# FanBot.net
KiCad netlist of a schematic drawn in Altium Designer
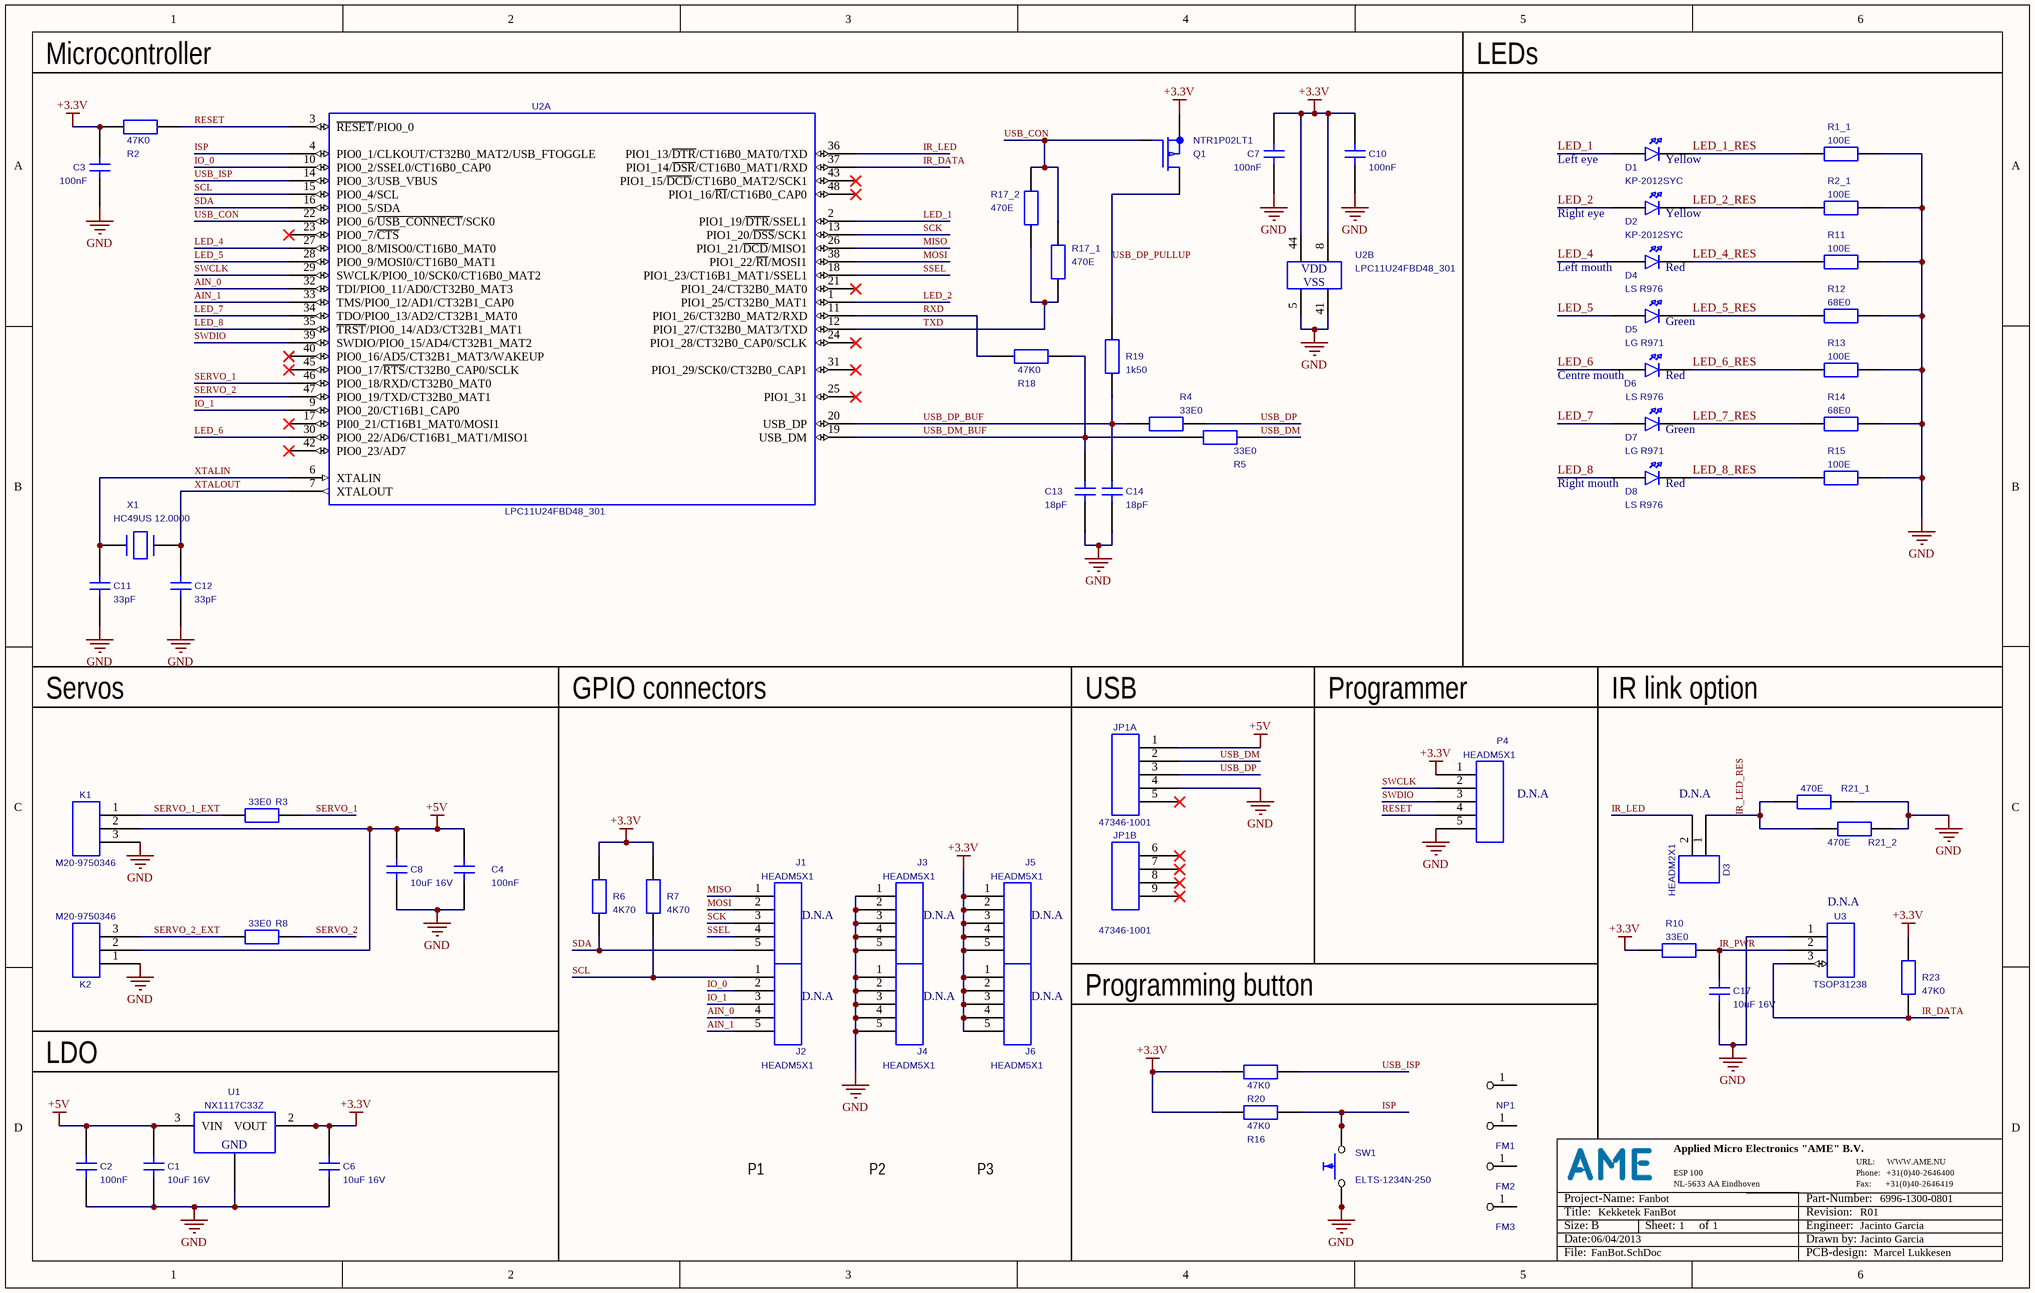
[diagram p0: FanBot.SchDoc]

(export (version "E")
  (design (tool "Eeschema 10.0.6"))
  (components
    (comp (ref "C1")
      (value "10U 0805 X5R16V")
      (footprint "C0805")
      (fields
        (field (name "PART NUMBER") "120400051105")
        (field (name "MANUFACTURER") "AVX")
        (field (name "PVALUE") "10uF 16V")
      )
      (libsource (lib "CC0805") (part "10U 0805 X5R16V"))
    )
    (comp (ref "C2")
      (value "100N 0805 X7R50V")
      (footprint "C0805")
      (fields
        (field (name "PVALUE") "100nF")
        (field (name "PART NUMBER") "120400011003")
        (field (name "MANUFACTURER") "Kemet")
      )
      (libsource (lib "CC0805") (part "100N 0805 X7R50V"))
    )
    (comp (ref "C3")
      (value "100N 0805 X7R50V")
      (footprint "C0805")
      (fields
        (field (name "PVALUE") "100nF")
        (field (name "PART NUMBER") "120400011003")
        (field (name "MANUFACTURER") "Kemet")
      )
      (libsource (lib "CC0805") (part "100N 0805 X7R50V"))
    )
    (comp (ref "C4")
      (value "100N 0805 X7R50V")
      (footprint "C0805")
      (fields
        (field (name "PVALUE") "100nF")
        (field (name "PART NUMBER") "120400011003")
        (field (name "MANUFACTURER") "Kemet")
      )
      (libsource (lib "CC0805") (part "100N 0805 X7R50V"))
    )
    (comp (ref "C6")
      (value "10U 0805 X5R16V")
      (footprint "C0805")
      (fields
        (field (name "PART NUMBER") "120400051105")
        (field (name "MANUFACTURER") "AVX")
        (field (name "PVALUE") "10uF 16V")
      )
      (libsource (lib "CC0805") (part "10U 0805 X5R16V"))
    )
    (comp (ref "C7")
      (value "100N 0805 X7R50V")
      (footprint "C0805")
      (fields
        (field (name "PVALUE") "100nF")
        (field (name "PART NUMBER") "120400011003")
        (field (name "MANUFACTURER") "Kemet")
      )
      (libsource (lib "CC0805") (part "100N 0805 X7R50V"))
    )
    (comp (ref "C8")
      (value "10U 0805 X5R16V")
      (footprint "C0805")
      (fields
        (field (name "PART NUMBER") "120400051105")
        (field (name "MANUFACTURER") "AVX")
        (field (name "PVALUE") "10uF 16V")
      )
      (libsource (lib "CC0805") (part "10U 0805 X5R16V"))
    )
    (comp (ref "C10")
      (value "100N 0805 X7R50V")
      (footprint "C0805")
      (fields
        (field (name "PVALUE") "100nF")
        (field (name "PART NUMBER") "120400011003")
        (field (name "MANUFACTURER") "Kemet")
      )
      (libsource (lib "CC0805") (part "100N 0805 X7R50V"))
    )
    (comp (ref "C11")
      (value "33P 0805 X7R50V")
      (footprint "C0805")
      (fields
        (field (name "PVALUE") "33pF")
        (field (name "PART NUMBER") "120400013309")
        (field (name "MANUFACTURER") "Kemet")
      )
      (libsource (lib "CC0805") (part "33P 0805 X7R50V"))
    )
    (comp (ref "C12")
      (value "33P 0805 X7R50V")
      (footprint "C0805")
      (fields
        (field (name "PVALUE") "33pF")
        (field (name "PART NUMBER") "120400013309")
        (field (name "MANUFACTURER") "Kemet")
      )
      (libsource (lib "CC0805") (part "33P 0805 X7R50V"))
    )
    (comp (ref "C13")
      (value "18P 0805 X7R50V")
      (footprint "C0805")
      (fields
        (field (name "PVALUE") "18pF")
        (field (name "PART NUMBER") "120400011809")
        (field (name "MANUFACTURER") "Kemet")
      )
      (libsource (lib "CC0805") (part "18P 0805 X7R50V"))
    )
    (comp (ref "C14")
      (value "18P 0805 X7R50V")
      (footprint "C0805")
      (fields
        (field (name "PVALUE") "18pF")
        (field (name "PART NUMBER") "120400011809")
        (field (name "MANUFACTURER") "Kemet")
      )
      (libsource (lib "CC0805") (part "18P 0805 X7R50V"))
    )
    (comp (ref "C17")
      (value "10U 0805 X5R16V")
      (footprint "C0805")
      (fields
        (field (name "PART NUMBER") "120400051105")
        (field (name "MANUFACTURER") "AVX")
        (field (name "PVALUE") "10uF 16V")
      )
      (libsource (lib "CC0805") (part "10U 0805 X5R16V"))
    )
    (comp (ref "D1")
      (value "KP-2012SYC")
      (footprint "0805 LED")
      (fields (field (name "PART NUMBER") "206000010035") (field (name "MANUFACTURER") "Kingbright"))
      (libsource (lib "DIS_AM") (part "KP-2012SYC"))
    )
    (comp (ref "D2")
      (value "KP-2012SYC")
      (footprint "0805 LED")
      (fields (field (name "PART NUMBER") "206000010035") (field (name "MANUFACTURER") "Kingbright"))
      (libsource (lib "DIS_AM") (part "KP-2012SYC"))
    )
    (comp (ref "D3")
      (value "HEADM2X1")
      (footprint "HEADM2X1")
      (fields (field (name "PART NUMBER") "505000030003") (field (name "MANUFACTURER") "Harwin"))
      (libsource (lib "CONN_AM") (part "HEADM2X1"))
    )
    (comp (ref "D4")
      (value "LS R976")
      (footprint "0805 LED OSR")
      (fields (field (name "PART NUMBER") "206000010024") (field (name "MANUFACTURER") "Osram"))
      (libsource (lib "DIS_AM") (part "LS R976"))
    )
    (comp (ref "D5")
      (value "LG R971")
      (footprint "0805 LED OSR")
      (fields (field (name "PART NUMBER") "206000010001") (field (name "MANUFACTURER") "Osram"))
      (libsource (lib "DIS_AM") (part "LG R971"))
    )
    (comp (ref "D6")
      (value "LS R976")
      (footprint "0805 LED OSR")
      (fields (field (name "PART NUMBER") "206000010024") (field (name "MANUFACTURER") "Osram"))
      (libsource (lib "DIS_AM") (part "LS R976"))
    )
    (comp (ref "D7")
      (value "LG R971")
      (footprint "0805 LED OSR")
      (fields (field (name "PART NUMBER") "206000010001") (field (name "MANUFACTURER") "Osram"))
      (libsource (lib "DIS_AM") (part "LG R971"))
    )
    (comp (ref "D8")
      (value "LS R976")
      (footprint "0805 LED OSR")
      (fields (field (name "PART NUMBER") "206000010024") (field (name "MANUFACTURER") "Osram"))
      (libsource (lib "DIS_AM") (part "LS R976"))
    )
    (comp (ref "FM1")
      (value "FIDUCIAL MARK 1")
      (footprint "FIDUCIAL MARK 1")
      (libsource (lib "SCH") (part "FIDUCIAL MARK 1"))
    )
    (comp (ref "FM2")
      (value "FIDUCIAL MARK 1")
      (footprint "FIDUCIAL MARK 1")
      (libsource (lib "SCH") (part "FIDUCIAL MARK 1"))
    )
    (comp (ref "FM3")
      (value "FIDUCIAL MARK 1")
      (footprint "FIDUCIAL MARK 1")
      (libsource (lib "SCH") (part "FIDUCIAL MARK 1"))
    )
    (comp (ref "J1")
      (value "HEADM5X1")
      (footprint "M20-9770522")
      (fields (field (name "PART NUMBER") "505000080023") (field (name "MANUFACTURER") "Harwin"))
      (libsource (lib "CONN_AM") (part "HEADM5X1"))
    )
    (comp (ref "J2")
      (value "HEADM5X1")
      (footprint "M20-9770522")
      (fields (field (name "PART NUMBER") "505000080023") (field (name "MANUFACTURER") "Harwin"))
      (libsource (lib "CONN_AM") (part "HEADM5X1"))
    )
    (comp (ref "J3")
      (value "HEADM5X1")
      (footprint "M20-9770522")
      (fields (field (name "PART NUMBER") "505000080023") (field (name "MANUFACTURER") "Harwin"))
      (libsource (lib "CONN_AM") (part "HEADM5X1"))
    )
    (comp (ref "J4")
      (value "HEADM5X1")
      (footprint "M20-9770522")
      (fields (field (name "PART NUMBER") "505000080023") (field (name "MANUFACTURER") "Harwin"))
      (libsource (lib "CONN_AM") (part "HEADM5X1"))
    )
    (comp (ref "J5")
      (value "HEADM5X1")
      (footprint "M20-9770522")
      (fields (field (name "PART NUMBER") "505000080023") (field (name "MANUFACTURER") "Harwin"))
      (libsource (lib "CONN_AM") (part "HEADM5X1"))
    )
    (comp (ref "J6")
      (value "HEADM5X1")
      (footprint "M20-9770522")
      (fields (field (name "PART NUMBER") "505000080023") (field (name "MANUFACTURER") "Harwin"))
      (libsource (lib "CONN_AM") (part "HEADM5X1"))
    )
    (comp (ref "JP1")
      (value "47346-1001")
      (footprint "47346-0001")
      (fields (field (name "PART NUMBER") "509000220067") (field (name "MANUFACTURER") "Molex"))
      (libsource (lib "CONN_AM") (part "47346-1001"))
    )
    (comp (ref "K1")
      (value "M20-9750346")
      (footprint "M20-9750346")
      (fields (field (name "PART NUMBER") "505000080120") (field (name "MANUFACTURER") "Harwin"))
      (libsource (lib "CONN_AM") (part "M20-9750346"))
    )
    (comp (ref "K2")
      (value "M20-9750346")
      (footprint "M20-9750346")
      (fields (field (name "PART NUMBER") "505000080120") (field (name "MANUFACTURER") "Harwin"))
      (libsource (lib "CONN_AM") (part "M20-9750346"))
    )
    (comp (ref "NP1") (value "NULPUNT") (footprint "NULPUNT") (libsource (lib "SCH") (part "NULPUNT")))
    (comp (ref "P4")
      (value "HEADM5X1")
      (footprint "M20-9770522")
      (fields (field (name "PART NUMBER") "505000080023") (field (name "MANUFACTURER") "Harwin"))
      (libsource (lib "CONN_AM") (part "HEADM5X1"))
    )
    (comp (ref "Q1")
      (value "NTR1P02LT1")
      (footprint "SOT-23")
      (fields (field (name "PART NUMBER") "222000010018") (field (name "MANUFACTURER") "ON Semiconductor"))
      (libsource (lib "DIS_AM") (part "NTR1P02LT1"))
    )
    (comp (ref "R1_1")
      (value "100E 0805 1%")
      (footprint "R0805")
      (fields
        (field (name "PVALUE") "100E")
        (field (name "PART NUMBER") "110200011000")
        (field (name "MANUFACTURER") "ASJ")
      )
      (libsource (lib "RM08051") (part "100E 0805 1%"))
    )
    (comp (ref "R2")
      (value "47K0 0805 1%")
      (footprint "R0805")
      (fields
        (field (name "PVALUE") "47K0")
        (field (name "PART NUMBER") "110200014702")
        (field (name "MANUFACTURER") "ASJ")
      )
      (libsource (lib "RM08051") (part "47K0 0805 1%"))
    )
    (comp (ref "R2_1")
      (value "100E 0805 1%")
      (footprint "R0805")
      (fields
        (field (name "PVALUE") "100E")
        (field (name "PART NUMBER") "110200011000")
        (field (name "MANUFACTURER") "ASJ")
      )
      (libsource (lib "RM08051") (part "100E 0805 1%"))
    )
    (comp (ref "R3")
      (value "33E0 0805 1%")
      (footprint "R0805")
      (fields
        (field (name "PART NUMBER") "110200013309")
        (field (name "MANUFACTURER") "Yageo")
        (field (name "PVALUE") "33E0")
      )
      (libsource (lib "RM08051") (part "33E0 0805 1%"))
    )
    (comp (ref "R4")
      (value "33E0 0805 1%")
      (footprint "R0805")
      (fields
        (field (name "PART NUMBER") "110200013309")
        (field (name "MANUFACTURER") "Yageo")
        (field (name "PVALUE") "33E0")
      )
      (libsource (lib "RM08051") (part "33E0 0805 1%"))
    )
    (comp (ref "R5")
      (value "33E0 0805 1%")
      (footprint "R0805")
      (fields
        (field (name "PART NUMBER") "110200013309")
        (field (name "MANUFACTURER") "Yageo")
        (field (name "PVALUE") "33E0")
      )
      (libsource (lib "RM08051") (part "33E0 0805 1%"))
    )
    (comp (ref "R6")
      (value "4K70 0805 1%")
      (footprint "R0805")
      (fields
        (field (name "PVALUE") "4K70")
        (field (name "PART NUMBER") "110200014701")
        (field (name "MANUFACTURER") "ASJ")
      )
      (libsource (lib "RM08051") (part "4K70 0805 1%"))
    )
    (comp (ref "R7")
      (value "4K70 0805 1%")
      (footprint "R0805")
      (fields
        (field (name "PVALUE") "4K70")
        (field (name "PART NUMBER") "110200014701")
        (field (name "MANUFACTURER") "ASJ")
      )
      (libsource (lib "RM08051") (part "4K70 0805 1%"))
    )
    (comp (ref "R8")
      (value "33E0 0805 1%")
      (footprint "R0805")
      (fields
        (field (name "PART NUMBER") "110200013309")
        (field (name "MANUFACTURER") "Yageo")
        (field (name "PVALUE") "33E0")
      )
      (libsource (lib "RM08051") (part "33E0 0805 1%"))
    )
    (comp (ref "R10")
      (value "33E0 0805 1%")
      (footprint "R0805")
      (fields
        (field (name "PVALUE") "33E0")
        (field (name "PART NUMBER") "110200013309")
        (field (name "MANUFACTURER") "Yageo")
      )
      (libsource (lib "RM08051") (part "33E0 0805 1%"))
    )
    (comp (ref "R11")
      (value "100E 0805 1%")
      (footprint "R0805")
      (fields
        (field (name "PVALUE") "100E")
        (field (name "PART NUMBER") "110200011000")
        (field (name "MANUFACTURER") "ASJ")
      )
      (libsource (lib "RM08051") (part "100E 0805 1%"))
    )
    (comp (ref "R12")
      (value "68E0 0805 1%")
      (footprint "R0805")
      (fields
        (field (name "PVALUE") "68E0")
        (field (name "PART NUMBER") "110200016809")
        (field (name "MANUFACTURER") "ASJ")
      )
      (libsource (lib "RM08051") (part "68E0 0805 1%"))
    )
    (comp (ref "R13")
      (value "100E 0805 1%")
      (footprint "R0805")
      (fields
        (field (name "PVALUE") "100E")
        (field (name "PART NUMBER") "110200011000")
        (field (name "MANUFACTURER") "ASJ")
      )
      (libsource (lib "RM08051") (part "100E 0805 1%"))
    )
    (comp (ref "R14")
      (value "68E0 0805 1%")
      (footprint "R0805")
      (fields
        (field (name "PVALUE") "68E0")
        (field (name "PART NUMBER") "110200016809")
        (field (name "MANUFACTURER") "ASJ")
      )
      (libsource (lib "RM08051") (part "68E0 0805 1%"))
    )
    (comp (ref "R15")
      (value "100E 0805 1%")
      (footprint "R0805")
      (fields
        (field (name "PVALUE") "100E")
        (field (name "PART NUMBER") "110200011000")
        (field (name "MANUFACTURER") "ASJ")
      )
      (libsource (lib "RM08051") (part "100E 0805 1%"))
    )
    (comp (ref "R16")
      (value "47K0 0805 1%")
      (footprint "R0805")
      (fields
        (field (name "PVALUE") "47K0")
        (field (name "PART NUMBER") "110200014702")
        (field (name "MANUFACTURER") "ASJ")
      )
      (libsource (lib "RM08051") (part "47K0 0805 1%"))
    )
    (comp (ref "R17_1")
      (value "470E 0805 1%")
      (footprint "R0805")
      (fields
        (field (name "PVALUE") "470E")
        (field (name "PART NUMBER") "110200014700")
        (field (name "MANUFACTURER") "ASJ")
      )
      (libsource (lib "RM08051") (part "470E 0805 1%"))
    )
    (comp (ref "R17_2")
      (value "470E 0805 1%")
      (footprint "R0805")
      (fields
        (field (name "PVALUE") "470E")
        (field (name "PART NUMBER") "110200014700")
        (field (name "MANUFACTURER") "ASJ")
      )
      (libsource (lib "RM08051") (part "470E 0805 1%"))
    )
    (comp (ref "R18")
      (value "47K0 0805 1%")
      (footprint "R0805")
      (fields
        (field (name "PVALUE") "47K0")
        (field (name "PART NUMBER") "110200014702")
        (field (name "MANUFACTURER") "ASJ")
      )
      (libsource (lib "RM08051") (part "47K0 0805 1%"))
    )
    (comp (ref "R19")
      (value "1K50 0805 1%")
      (footprint "R0805")
      (fields
        (field (name "PVALUE") "1k50")
        (field (name "PART NUMBER") "110200011501")
        (field (name "MANUFACTURER") "ASJ")
      )
      (libsource (lib "RM08051") (part "1K50 0805 1%"))
    )
    (comp (ref "R20")
      (value "47K0 0805 1%")
      (footprint "R0805")
      (fields
        (field (name "PVALUE") "47K0")
        (field (name "PART NUMBER") "110200014702")
        (field (name "MANUFACTURER") "ASJ")
      )
      (libsource (lib "RM08051") (part "47K0 0805 1%"))
    )
    (comp (ref "R21_1")
      (value "470E 0805 1%")
      (footprint "R0805")
      (fields
        (field (name "PVALUE") "470E")
        (field (name "PART NUMBER") "110200014700")
        (field (name "MANUFACTURER") "ASJ")
      )
      (libsource (lib "RM08051") (part "470E 0805 1%"))
    )
    (comp (ref "R21_2")
      (value "470E 0805 1%")
      (footprint "R0805")
      (fields
        (field (name "PVALUE") "470E")
        (field (name "PART NUMBER") "110200014700")
        (field (name "MANUFACTURER") "ASJ")
      )
      (libsource (lib "RM08051") (part "470E 0805 1%"))
    )
    (comp (ref "R23")
      (value "47K0 0805 1%")
      (footprint "R0805")
      (fields
        (field (name "PVALUE") "47K0")
        (field (name "PART NUMBER") "110200014702")
        (field (name "MANUFACTURER") "ASJ")
      )
      (libsource (lib "RM08051") (part "47K0 0805 1%"))
    )
    (comp (ref "SW1")
      (value "ELTS-1234N-250")
      (footprint "ELTS-1234N")
      (fields (field (name "PART NUMBER") "513000010022") (field (name "MANUFACTURER") "Eledis"))
      (libsource (lib "ELEC_AM") (part "ELTS-1234N-250"))
    )
    (comp (ref "U1")
      (value "NX1117C33Z")
      (footprint "SOT-223")
      (fields (field (name "PART NUMBER") "330000010048") (field (name "MANUFACTURER") "NXP Semiconductor"))
      (libsource (lib "REGULATORS") (part "NX1117C33Z"))
    )
    (comp (ref "U2")
      (value "LPC11U24FBD48_301")
      (footprint "LQFP48")
      (fields (field (name "PART NUMBER") "411000010007") (field (name "MANUFACTURER") "NXP Semiconductor"))
      (libsource (lib "MICRO") (part "LPC11U24FBD48_301"))
    )
    (comp (ref "U3")
      (value "TSOP31238")
      (footprint "TSOP312")
      (fields (field (name "PART NUMBER") "324000010007") (field (name "MANUFACTURER") "Vishay"))
      (libsource (lib "DIS_AM") (part "TSOP31238"))
    )
    (comp (ref "X1")
      (value "HC49US 12.0000")
      (footprint "HC49/4HSMX")
      (fields (field (name "PART NUMBER") "140000010015") (field (name "MANUFACTURER") "Hong Kong Crystals"))
      (libsource (lib "XTAL") (part "HC49US 12.0000"))
    )
  )
  (nets
    (net (code "1") (name "+3.3V") (class "Default")
      (node (ref "C10") (pin "1") (pinfunction "1_1") (pintype "passive"))
      (node (ref "C3") (pin "1") (pinfunction "1_1") (pintype "passive"))
      (node (ref "C6") (pin "1") (pinfunction "1_1") (pintype "passive"))
      (node (ref "C7") (pin "1") (pinfunction "1_1") (pintype "passive"))
      (node (ref "J5") (pin "1") (pinfunction "A1_1") (pintype "passive"))
      (node (ref "J5") (pin "2") (pinfunction "A2_2") (pintype "passive"))
      (node (ref "J5") (pin "3") (pinfunction "A3_3") (pintype "passive"))
      (node (ref "J5") (pin "4") (pinfunction "A4_4") (pintype "passive"))
      (node (ref "J5") (pin "5") (pinfunction "A5_5") (pintype "passive"))
      (node (ref "J6") (pin "1") (pinfunction "A1_1") (pintype "passive"))
      (node (ref "J6") (pin "2") (pinfunction "A2_2") (pintype "passive"))
      (node (ref "J6") (pin "3") (pinfunction "A3_3") (pintype "passive"))
      (node (ref "J6") (pin "4") (pinfunction "A4_4") (pintype "passive"))
      (node (ref "J6") (pin "5") (pinfunction "A5_5") (pintype "passive"))
      (node (ref "P4") (pin "1") (pinfunction "A1_1") (pintype "passive"))
      (node (ref "Q1") (pin "2") (pinfunction "S_2") (pintype "passive"))
      (node (ref "R10") (pin "1") (pinfunction "1_1") (pintype "passive"))
      (node (ref "R16") (pin "2") (pinfunction "2_2") (pintype "passive"))
      (node (ref "R2") (pin "2") (pinfunction "2_2") (pintype "passive"))
      (node (ref "R20") (pin "2") (pinfunction "2_2") (pintype "passive"))
      (node (ref "R23") (pin "1") (pinfunction "1_1") (pintype "passive"))
      (node (ref "R6") (pin "1") (pinfunction "1_1") (pintype "passive"))
      (node (ref "R7") (pin "1") (pinfunction "1_1") (pintype "passive"))
      (node (ref "U1") (pin "2") (pinfunction "VOUT_2") (pintype "power_in"))
      (node (ref "U1") (pin "4") (pinfunction "VOUT_4") (pintype "power_in"))
      (node (ref "U2") (pin "44") (pinfunction "VDD_44") (pintype "power_in"))
      (node (ref "U2") (pin "8") (pinfunction "VDD_8") (pintype "power_in"))
    )
    (net (code "2") (name "+5V") (class "Default")
      (node (ref "C1") (pin "1") (pinfunction "1_1") (pintype "passive"))
      (node (ref "C2") (pin "1") (pinfunction "1_1") (pintype "passive"))
      (node (ref "C4") (pin "1") (pinfunction "1_1") (pintype "passive"))
      (node (ref "C8") (pin "1") (pinfunction "1_1") (pintype "passive"))
      (node (ref "JP1") (pin "1") (pinfunction "VBUS_1") (pintype "passive"))
      (node (ref "K1") (pin "2") (pinfunction "2_2") (pintype "passive"))
      (node (ref "K2") (pin "2") (pinfunction "2_2") (pintype "passive"))
      (node (ref "U1") (pin "3") (pinfunction "VIN_3") (pintype "power_in"))
    )
    (net (code "3") (name "/AIN_0") (class "Default")
      (node (ref "J2") (pin "4") (pinfunction "A4_4") (pintype "passive"))
      (node (ref "U2") (pin "32") (pinfunction "TDI/PIO0_11/AD0/CT32B0_MAT3_32") (pintype "bidirectional"))
    )
    (net (code "4") (name "/AIN_1") (class "Default")
      (node (ref "J2") (pin "5") (pinfunction "A5_5") (pintype "passive"))
      (node (ref "U2") (pin "33") (pinfunction "TMS/PIO0_12/AD1/CT32B1_CAP0_33") (pintype "bidirectional"))
    )
    (net (code "5") (name "/IO_0") (class "Default")
      (node (ref "J2") (pin "2") (pinfunction "A2_2") (pintype "passive"))
      (node (ref "U2") (pin "10") (pinfunction "PIO0_2/SSEL0/CT16B0_CAP0_10") (pintype "bidirectional"))
    )
    (net (code "6") (name "/IO_1") (class "Default")
      (node (ref "J2") (pin "3") (pinfunction "A3_3") (pintype "passive"))
      (node (ref "U2") (pin "9") (pinfunction "PIO0_20/CT16B1_CAP0_9") (pintype "bidirectional"))
    )
    (net (code "7") (name "/IR_DATA") (class "Default")
      (node (ref "R23") (pin "2") (pinfunction "2_2") (pintype "passive"))
      (node (ref "U2") (pin "37") (pinfunction "PIO1_14/~{DSR}/CT16B0_MAT1/RXD_37") (pintype "bidirectional"))
      (node (ref "U3") (pin "3") (pinfunction "OUT_3") (pintype "bidirectional"))
    )
    (net (code "8") (name "/IR_LED") (class "Default")
      (node (ref "D3") (pin "2") (pintype "passive"))
      (node (ref "U2") (pin "36") (pinfunction "PIO1_13/~{DTR}/CT16B0_MAT0/TXD_36") (pintype "bidirectional"))
    )
    (net (code "9") (name "/IR_LED_RES") (class "Default")
      (node (ref "D3") (pin "1") (pintype "passive"))
      (node (ref "R21_1") (pin "1") (pinfunction "1_1") (pintype "passive"))
      (node (ref "R21_2") (pin "1") (pinfunction "1_1") (pintype "passive"))
    )
    (net (code "10") (name "/IR_PWR") (class "Default")
      (node (ref "C17") (pin "1") (pinfunction "1_1") (pintype "passive"))
      (node (ref "R10") (pin "2") (pinfunction "2_2") (pintype "passive"))
      (node (ref "U3") (pin "2") (pinfunction "VS_2") (pintype "power_in"))
    )
    (net (code "11") (name "/ISP") (class "Default")
      (node (ref "R16") (pin "1") (pinfunction "1_1") (pintype "passive"))
      (node (ref "SW1") (pin "1") (pintype "passive"))
      (node (ref "SW1") (pin "3") (pintype "passive"))
      (node (ref "U2") (pin "4") (pinfunction "PIO0_1/CLKOUT/CT32B0_MAT2/USB_FTOGGLE_4") (pintype "bidirectional"))
    )
    (net (code "12") (name "/LED_1") (class "Default")
      (node (ref "D1") (pin "2") (pinfunction "A_2") (pintype "passive"))
      (node (ref "U2") (pin "2") (pinfunction "PIO1_19/~{DTR}/SSEL1_2") (pintype "bidirectional"))
    )
    (net (code "13") (name "/LED_1_RES") (class "Default")
      (node (ref "D1") (pin "1") (pinfunction "K_1") (pintype "passive"))
      (node (ref "R1_1") (pin "1") (pinfunction "1_1") (pintype "passive"))
    )
    (net (code "14") (name "/LED_2") (class "Default")
      (node (ref "D2") (pin "2") (pinfunction "A_2") (pintype "passive"))
      (node (ref "U2") (pin "1") (pinfunction "PIO1_25/CT32B0_MAT1_1") (pintype "bidirectional"))
    )
    (net (code "15") (name "/LED_2_RES") (class "Default")
      (node (ref "D2") (pin "1") (pinfunction "K_1") (pintype "passive"))
      (node (ref "R2_1") (pin "1") (pinfunction "1_1") (pintype "passive"))
    )
    (net (code "16") (name "/LED_4") (class "Default")
      (node (ref "D4") (pin "2") (pinfunction "A_2") (pintype "passive"))
      (node (ref "U2") (pin "27") (pinfunction "PIO0_8/MISO0/CT16B0_MAT0_27") (pintype "bidirectional"))
    )
    (net (code "17") (name "/LED_4_RES") (class "Default")
      (node (ref "D4") (pin "1") (pinfunction "K_1") (pintype "passive"))
      (node (ref "R11") (pin "1") (pinfunction "1_1") (pintype "passive"))
    )
    (net (code "18") (name "/LED_5") (class "Default")
      (node (ref "D5") (pin "2") (pinfunction "A_2") (pintype "passive"))
      (node (ref "U2") (pin "28") (pinfunction "PIO0_9/MOSI0/CT16B0_MAT1_28") (pintype "bidirectional"))
    )
    (net (code "19") (name "/LED_5_RES") (class "Default")
      (node (ref "D5") (pin "1") (pinfunction "K_1") (pintype "passive"))
      (node (ref "R12") (pin "1") (pinfunction "1_1") (pintype "passive"))
    )
    (net (code "20") (name "/LED_6") (class "Default")
      (node (ref "D6") (pin "2") (pinfunction "A_2") (pintype "passive"))
      (node (ref "U2") (pin "30") (pinfunction "PIO0_22/AD6/CT16B1_MAT1/MISO1_30") (pintype "bidirectional"))
    )
    (net (code "21") (name "/LED_6_RES") (class "Default")
      (node (ref "D6") (pin "1") (pinfunction "K_1") (pintype "passive"))
      (node (ref "R13") (pin "1") (pinfunction "1_1") (pintype "passive"))
    )
    (net (code "22") (name "/LED_7") (class "Default")
      (node (ref "D7") (pin "2") (pinfunction "A_2") (pintype "passive"))
      (node (ref "U2") (pin "34") (pinfunction "TDO/PIO0_13/AD2/CT32B1_MAT0_34") (pintype "bidirectional"))
    )
    (net (code "23") (name "/LED_7_RES") (class "Default")
      (node (ref "D7") (pin "1") (pinfunction "K_1") (pintype "passive"))
      (node (ref "R14") (pin "1") (pinfunction "1_1") (pintype "passive"))
    )
    (net (code "24") (name "/LED_8") (class "Default")
      (node (ref "D8") (pin "2") (pinfunction "A_2") (pintype "passive"))
      (node (ref "U2") (pin "35") (pinfunction "~{TRST}/PIO0_14/AD3/CT32B1_MAT1_35") (pintype "bidirectional"))
    )
    (net (code "25") (name "/LED_8_RES") (class "Default")
      (node (ref "D8") (pin "1") (pinfunction "K_1") (pintype "passive"))
      (node (ref "R15") (pin "1") (pinfunction "1_1") (pintype "passive"))
    )
    (net (code "26") (name "/MISO") (class "Default")
      (node (ref "J1") (pin "1") (pinfunction "A1_1") (pintype "passive"))
      (node (ref "U2") (pin "26") (pinfunction "PIO1_21/~{DCD}/MISO1_26") (pintype "bidirectional"))
    )
    (net (code "27") (name "/MOSI") (class "Default")
      (node (ref "J1") (pin "2") (pinfunction "A2_2") (pintype "passive"))
      (node (ref "U2") (pin "38") (pinfunction "PIO1_22/~{RI}/MOSI1_38") (pintype "bidirectional"))
    )
    (net (code "28") (name "/RESET") (class "Default")
      (node (ref "P4") (pin "4") (pinfunction "A4_4") (pintype "passive"))
      (node (ref "R2") (pin "1") (pinfunction "1_1") (pintype "passive"))
      (node (ref "U2") (pin "3") (pinfunction "~{RESET}/PIO0_0_3") (pintype "bidirectional"))
    )
    (net (code "29") (name "/RXD") (class "Default")
      (node (ref "R18") (pin "2") (pinfunction "2_2") (pintype "passive"))
      (node (ref "U2") (pin "11") (pinfunction "PIO1_26/CT32B0_MAT2/RXD_11") (pintype "bidirectional"))
    )
    (net (code "30") (name "/SCK") (class "Default")
      (node (ref "J1") (pin "3") (pinfunction "A3_3") (pintype "passive"))
      (node (ref "U2") (pin "13") (pinfunction "PIO1_20/~{DSS}/SCK1_13") (pintype "bidirectional"))
    )
    (net (code "31") (name "/SCL") (class "Default")
      (node (ref "J2") (pin "1") (pinfunction "A1_1") (pintype "passive"))
      (node (ref "R7") (pin "2") (pinfunction "2_2") (pintype "passive"))
      (node (ref "U2") (pin "15") (pinfunction "PIO0_4/SCL_15") (pintype "bidirectional"))
    )
    (net (code "32") (name "/SDA") (class "Default")
      (node (ref "J1") (pin "5") (pinfunction "A5_5") (pintype "passive"))
      (node (ref "R6") (pin "2") (pinfunction "2_2") (pintype "passive"))
      (node (ref "U2") (pin "16") (pinfunction "PIO0_5/SDA_16") (pintype "bidirectional"))
    )
    (net (code "33") (name "/SERVO_1") (class "Default")
      (node (ref "R3") (pin "2") (pinfunction "2_2") (pintype "passive"))
      (node (ref "U2") (pin "46") (pinfunction "PIO0_18/RXD/CT32B0_MAT0_46") (pintype "bidirectional"))
    )
    (net (code "34") (name "/SERVO_1_EXT") (class "Default")
      (node (ref "K1") (pin "1") (pinfunction "1_1") (pintype "passive"))
      (node (ref "R3") (pin "1") (pinfunction "1_1") (pintype "passive"))
    )
    (net (code "35") (name "/SERVO_2") (class "Default")
      (node (ref "R8") (pin "2") (pinfunction "2_2") (pintype "passive"))
      (node (ref "U2") (pin "47") (pinfunction "PIO0_19/TXD/CT32B0_MAT1_47") (pintype "bidirectional"))
    )
    (net (code "36") (name "/SERVO_2_EXT") (class "Default")
      (node (ref "K2") (pin "3") (pinfunction "3_3") (pintype "passive"))
      (node (ref "R8") (pin "1") (pinfunction "1_1") (pintype "passive"))
    )
    (net (code "37") (name "/SSEL") (class "Default")
      (node (ref "J1") (pin "4") (pinfunction "A4_4") (pintype "passive"))
      (node (ref "U2") (pin "18") (pinfunction "PIO1_23/CT16B1_MAT1/SSEL1_18") (pintype "bidirectional"))
    )
    (net (code "38") (name "/SWCLK") (class "Default")
      (node (ref "P4") (pin "2") (pinfunction "A2_2") (pintype "passive"))
      (node (ref "U2") (pin "29") (pinfunction "SWCLK/PIO0_10/SCK0/CT16B0_MAT2_29") (pintype "bidirectional"))
    )
    (net (code "39") (name "/SWDIO") (class "Default")
      (node (ref "P4") (pin "3") (pinfunction "A3_3") (pintype "passive"))
      (node (ref "U2") (pin "39") (pinfunction "SWDIO/PIO0_15/AD4/CT32B1_MAT2_39") (pintype "bidirectional"))
    )
    (net (code "40") (name "/TXD") (class "Default")
      (node (ref "R17_1") (pin "2") (pinfunction "2_2") (pintype "passive"))
      (node (ref "R17_2") (pin "2") (pinfunction "2_2") (pintype "passive"))
      (node (ref "U2") (pin "12") (pinfunction "PIO1_27/CT32B0_MAT3/TXD_12") (pintype "bidirectional"))
    )
    (net (code "41") (name "/USB_CON") (class "Default")
      (node (ref "Q1") (pin "1") (pinfunction "G_1") (pintype "passive"))
      (node (ref "R17_1") (pin "1") (pinfunction "1_1") (pintype "passive"))
      (node (ref "R17_2") (pin "1") (pinfunction "1_1") (pintype "passive"))
      (node (ref "U2") (pin "22") (pinfunction "PIO0_6/~{USB_CONNECT}/SCK0_22") (pintype "bidirectional"))
    )
    (net (code "42") (name "/USB_DM") (class "Default")
      (node (ref "JP1") (pin "2") (pinfunction "D-_2") (pintype "passive"))
      (node (ref "R5") (pin "2") (pinfunction "2_2") (pintype "passive"))
    )
    (net (code "43") (name "/USB_DM_BUF") (class "Default")
      (node (ref "C13") (pin "1") (pinfunction "1_1") (pintype "passive"))
      (node (ref "R18") (pin "1") (pinfunction "1_1") (pintype "passive"))
      (node (ref "R5") (pin "1") (pinfunction "1_1") (pintype "passive"))
      (node (ref "U2") (pin "19") (pinfunction "USB_DM_19") (pintype "bidirectional"))
    )
    (net (code "44") (name "/USB_DP") (class "Default")
      (node (ref "JP1") (pin "3") (pinfunction "D+_3") (pintype "passive"))
      (node (ref "R4") (pin "2") (pinfunction "2_2") (pintype "passive"))
    )
    (net (code "45") (name "/USB_DP_BUF") (class "Default")
      (node (ref "C14") (pin "1") (pinfunction "1_1") (pintype "passive"))
      (node (ref "R19") (pin "2") (pinfunction "2_2") (pintype "passive"))
      (node (ref "R4") (pin "1") (pinfunction "1_1") (pintype "passive"))
      (node (ref "U2") (pin "20") (pinfunction "USB_DP_20") (pintype "bidirectional"))
    )
    (net (code "46") (name "/USB_DP_PULLUP") (class "Default")
      (node (ref "Q1") (pin "3") (pinfunction "D_3") (pintype "passive"))
      (node (ref "R19") (pin "1") (pinfunction "1_1") (pintype "passive"))
    )
    (net (code "47") (name "/USB_ISP") (class "Default")
      (node (ref "R20") (pin "1") (pinfunction "1_1") (pintype "passive"))
      (node (ref "U2") (pin "14") (pinfunction "PIO0_3/USB_VBUS_14") (pintype "bidirectional"))
    )
    (net (code "48") (name "/XTALIN") (class "Default")
      (node (ref "C11") (pin "1") (pinfunction "1_1") (pintype "passive"))
      (node (ref "U2") (pin "6") (pinfunction "XTALIN_6") (pintype "input"))
      (node (ref "X1") (pin "1") (pintype "passive"))
    )
    (net (code "49") (name "/XTALOUT") (class "Default")
      (node (ref "C12") (pin "1") (pinfunction "1_1") (pintype "passive"))
      (node (ref "U2") (pin "7") (pinfunction "XTALOUT_7") (pintype "output"))
      (node (ref "X1") (pin "2") (pintype "passive"))
    )
    (net (code "50") (name "GND") (class "Default")
      (node (ref "C1") (pin "2") (pinfunction "2_2") (pintype "passive"))
      (node (ref "C10") (pin "2") (pinfunction "2_2") (pintype "passive"))
      (node (ref "C11") (pin "2") (pinfunction "2_2") (pintype "passive"))
      (node (ref "C12") (pin "2") (pinfunction "2_2") (pintype "passive"))
      (node (ref "C13") (pin "2") (pinfunction "2_2") (pintype "passive"))
      (node (ref "C14") (pin "2") (pinfunction "2_2") (pintype "passive"))
      (node (ref "C17") (pin "2") (pinfunction "2_2") (pintype "passive"))
      (node (ref "C2") (pin "2") (pinfunction "2_2") (pintype "passive"))
      (node (ref "C3") (pin "2") (pinfunction "2_2") (pintype "passive"))
      (node (ref "C4") (pin "2") (pinfunction "2_2") (pintype "passive"))
      (node (ref "C6") (pin "2") (pinfunction "2_2") (pintype "passive"))
      (node (ref "C7") (pin "2") (pinfunction "2_2") (pintype "passive"))
      (node (ref "C8") (pin "2") (pinfunction "2_2") (pintype "passive"))
      (node (ref "J3") (pin "1") (pinfunction "A1_1") (pintype "passive"))
      (node (ref "J3") (pin "2") (pinfunction "A2_2") (pintype "passive"))
      (node (ref "J3") (pin "3") (pinfunction "A3_3") (pintype "passive"))
      (node (ref "J3") (pin "4") (pinfunction "A4_4") (pintype "passive"))
      (node (ref "J3") (pin "5") (pinfunction "A5_5") (pintype "passive"))
      (node (ref "J4") (pin "1") (pinfunction "A1_1") (pintype "passive"))
      (node (ref "J4") (pin "2") (pinfunction "A2_2") (pintype "passive"))
      (node (ref "J4") (pin "3") (pinfunction "A3_3") (pintype "passive"))
      (node (ref "J4") (pin "4") (pinfunction "A4_4") (pintype "passive"))
      (node (ref "J4") (pin "5") (pinfunction "A5_5") (pintype "passive"))
      (node (ref "JP1") (pin "4") (pinfunction "ID_4") (pintype "passive"))
      (node (ref "K1") (pin "3") (pinfunction "3_3") (pintype "passive"))
      (node (ref "K2") (pin "1") (pinfunction "1_1") (pintype "passive"))
      (node (ref "P4") (pin "5") (pinfunction "A5_5") (pintype "passive"))
      (node (ref "R11") (pin "2") (pinfunction "2_2") (pintype "passive"))
      (node (ref "R12") (pin "2") (pinfunction "2_2") (pintype "passive"))
      (node (ref "R13") (pin "2") (pinfunction "2_2") (pintype "passive"))
      (node (ref "R14") (pin "2") (pinfunction "2_2") (pintype "passive"))
      (node (ref "R15") (pin "2") (pinfunction "2_2") (pintype "passive"))
      (node (ref "R1_1") (pin "2") (pinfunction "2_2") (pintype "passive"))
      (node (ref "R21_1") (pin "2") (pinfunction "2_2") (pintype "passive"))
      (node (ref "R21_2") (pin "2") (pinfunction "2_2") (pintype "passive"))
      (node (ref "R2_1") (pin "2") (pinfunction "2_2") (pintype "passive"))
      (node (ref "SW1") (pin "2") (pintype "passive"))
      (node (ref "SW1") (pin "4") (pintype "passive"))
      (node (ref "U1") (pin "1") (pinfunction "ADJ/GND_1") (pintype "power_in"))
      (node (ref "U2") (pin "41") (pinfunction "VSS_41") (pintype "power_in"))
      (node (ref "U2") (pin "5") (pinfunction "VSS_5") (pintype "power_in"))
      (node (ref "U3") (pin "1") (pinfunction "GND_1") (pintype "power_in"))
    )
    (net (code "51") (name "unconnected-(FM1-Pad1)") (class "Default")
      (node (ref "FM1") (pin "1") (pintype "passive"))
    )
    (net (code "52") (name "unconnected-(FM2-Pad1)") (class "Default")
      (node (ref "FM2") (pin "1") (pintype "passive"))
    )
    (net (code "53") (name "unconnected-(FM3-Pad1)") (class "Default")
      (node (ref "FM3") (pin "1") (pintype "passive"))
    )
    (net (code "54") (name "unconnected-(JP1A-GND-Pad5)") (class "Default")
      (node (ref "JP1") (pin "5") (pinfunction "GND_5") (pintype "passive+no_connect"))
    )
    (net (code "55") (name "unconnected-(JP1B-SHIELD-Pad6)") (class "Default")
      (node (ref "JP1") (pin "6") (pinfunction "SHIELD_6") (pintype "passive+no_connect"))
    )
    (net (code "56") (name "unconnected-(JP1B-SHIELD-Pad7)") (class "Default")
      (node (ref "JP1") (pin "7") (pinfunction "SHIELD_7") (pintype "passive+no_connect"))
    )
    (net (code "57") (name "unconnected-(JP1B-SHIELD-Pad8)") (class "Default")
      (node (ref "JP1") (pin "8") (pinfunction "SHIELD_8") (pintype "passive+no_connect"))
    )
    (net (code "58") (name "unconnected-(JP1B-SHIELD-Pad9)") (class "Default")
      (node (ref "JP1") (pin "9") (pinfunction "SHIELD_9") (pintype "passive+no_connect"))
    )
    (net (code "59") (name "unconnected-(NP1-Pad1)") (class "Default")
      (node (ref "NP1") (pin "1") (pintype "passive"))
    )
    (net (code "60") (name "unconnected-(U2A-PI00_21{slash}CT16B1_MAT0{slash}MOSI1-Pad17)") (class "Default")
      (node (ref "U2") (pin "17") (pinfunction "PI00_21/CT16B1_MAT0/MOSI1_17") (pintype "bidirectional+no_connect"))
    )
    (net (code "61") (name "unconnected-(U2A-PIO0_7{slash}~{CTS}-Pad23)") (class "Default")
      (node (ref "U2") (pin "23") (pinfunction "PIO0_7/~{CTS}_23") (pintype "bidirectional+no_connect"))
    )
    (net (code "62") (name "unconnected-(U2A-PIO0_16{slash}AD5{slash}CT32B1_MAT3{slash}WAKEUP-Pad40)") (class "Default")
      (node (ref "U2") (pin "40") (pinfunction "PIO0_16/AD5/CT32B1_MAT3/WAKEUP_40") (pintype "bidirectional+no_connect"))
    )
    (net (code "63") (name "unconnected-(U2A-PIO0_17{slash}~{RTS}{slash}CT32B0_CAP0{slash}SCLK-Pad45)") (class "Default")
      (node (ref "U2") (pin "45") (pinfunction "PIO0_17/~{RTS}/CT32B0_CAP0/SCLK_45") (pintype "bidirectional+no_connect"))
    )
    (net (code "64") (name "unconnected-(U2A-PIO0_23{slash}AD7-Pad42)") (class "Default")
      (node (ref "U2") (pin "42") (pinfunction "PIO0_23/AD7_42") (pintype "bidirectional+no_connect"))
    )
    (net (code "65") (name "unconnected-(U2A-PIO1_15{slash}~{DCD}{slash}CT16B0_MAT2{slash}SCK1-Pad43)") (class "Default")
      (node (ref "U2") (pin "43") (pinfunction "PIO1_15/~{DCD}/CT16B0_MAT2/SCK1_43") (pintype "bidirectional+no_connect"))
    )
    (net (code "66") (name "unconnected-(U2A-PIO1_16{slash}~{RI}{slash}CT16B0_CAP0-Pad48)") (class "Default")
      (node (ref "U2") (pin "48") (pinfunction "PIO1_16/~{RI}/CT16B0_CAP0_48") (pintype "bidirectional+no_connect"))
    )
    (net (code "67") (name "unconnected-(U2A-PIO1_24{slash}CT32B0_MAT0-Pad21)") (class "Default")
      (node (ref "U2") (pin "21") (pinfunction "PIO1_24/CT32B0_MAT0_21") (pintype "bidirectional+no_connect"))
    )
    (net (code "68") (name "unconnected-(U2A-PIO1_28{slash}CT32B0_CAP0{slash}SCLK-Pad24)") (class "Default")
      (node (ref "U2") (pin "24") (pinfunction "PIO1_28/CT32B0_CAP0/SCLK_24") (pintype "bidirectional+no_connect"))
    )
    (net (code "69") (name "unconnected-(U2A-PIO1_29{slash}SCK0{slash}CT32B0_CAP1-Pad31)") (class "Default")
      (node (ref "U2") (pin "31") (pinfunction "PIO1_29/SCK0/CT32B0_CAP1_31") (pintype "bidirectional+no_connect"))
    )
    (net (code "70") (name "unconnected-(U2A-PIO1_31-Pad25)") (class "Default")
      (node (ref "U2") (pin "25") (pinfunction "PIO1_31_25") (pintype "bidirectional+no_connect"))
    )
  )
)
